# Sheet2.net
KiCad netlist of a schematic drawn in Altium Designer
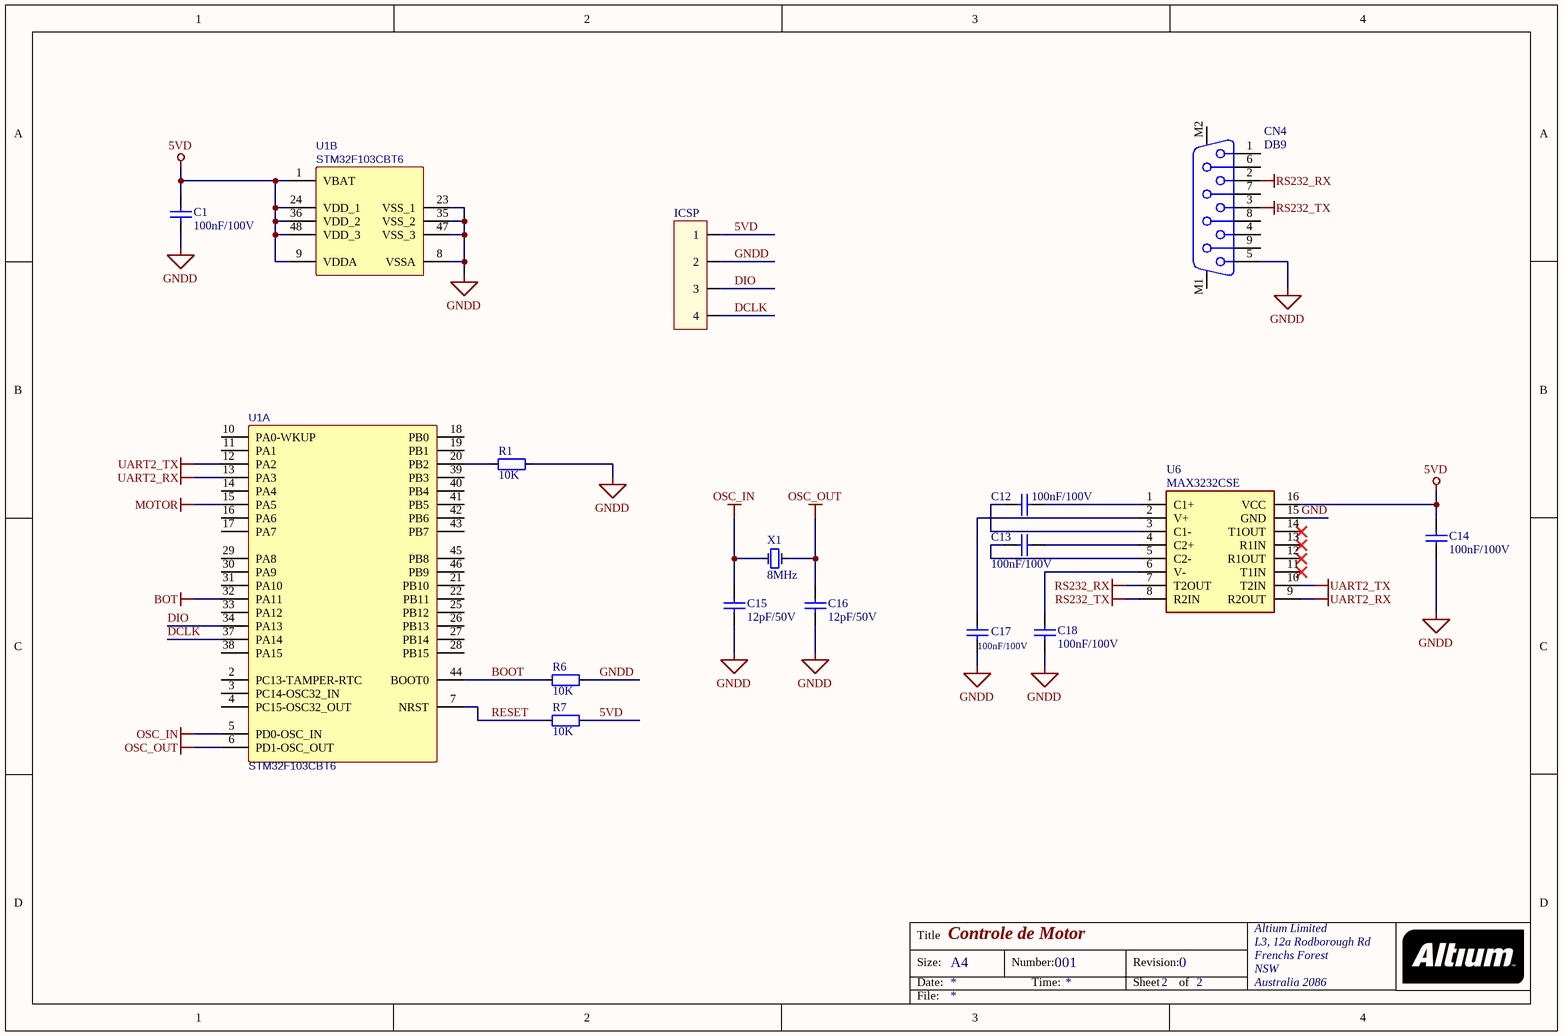
[diagram p0: Sheet2.SchDoc]

(export (version "E")
  (design (tool "Eeschema 10.0.6"))
  (components
    (comp (ref "C1")
      (value "100nF/100V")
      (footprint "0603C-GENERIC")
      (description "Capacitor Cerâmico SMD")
      (libsource (lib "Schlib") (part "Cap Ceramico SMD"))
    )
    (comp (ref "C12")
      (value "100nF/100V")
      (footprint "0603C-GENERIC")
      (description "Capacitor Cerâmico SMD")
      (libsource (lib "Schlib") (part "Cap Ceramico SMD"))
    )
    (comp (ref "C13")
      (value "100nF/100V")
      (footprint "0603C-GENERIC")
      (description "Capacitor Cerâmico SMD")
      (libsource (lib "Schlib") (part "Cap Ceramico SMD"))
    )
    (comp (ref "C14")
      (value "100nF/100V")
      (footprint "0603C-GENERIC")
      (description "Capacitor Cerâmico SMD")
      (libsource (lib "Schlib") (part "Cap Ceramico SMD"))
    )
    (comp (ref "C15")
      (value "12pF/50V")
      (footprint "0603C-GENERIC")
      (description "Capacitor Cerâmico")
      (libsource (lib "Miscellaneous Devices") (part "Cap Ceramico SMD"))
    )
    (comp (ref "C16")
      (value "12pF/50V")
      (footprint "0603C-GENERIC")
      (description "Capacitor Cerâmico")
      (libsource (lib "Miscellaneous Devices") (part "Cap Ceramico SMD"))
    )
    (comp (ref "C17")
      (value "100nF/100V")
      (footprint "0603C-GENERIC")
      (description "Capacitor Cerâmico SMD")
      (libsource (lib "Schlib") (part "Cap Ceramico SMD"))
    )
    (comp (ref "C18")
      (value "100nF/100V")
      (footprint "0603C-GENERIC")
      (description "Capacitor Cerâmico SMD")
      (libsource (lib "Schlib") (part "Cap Ceramico SMD"))
    )
    (comp (ref "CN4")
      (value "DB9")
      (footprint "618009231121")
      (description "Connector DB9")
      (libsource (lib "PUR Conectores") (part "DB9"))
    )
    (comp (ref "ICSP")
      (value "Gravação in circuit")
      (footprint "BP 1x4")
      (description "Barra de Pinos Macho 4p 11,2mm 180º")
      (libsource (lib "Schlib1") (part "BP 1x4 Pinos"))
    )
    (comp (ref "R1")
      (value "10K")
      (footprint "0603R")
      (description "Resistor Metal Filme")
      (libsource (lib "") (part "Res SMD 1206_1"))
    )
    (comp (ref "R6")
      (value "10K")
      (footprint "0603R")
      (description "Resistor Metal Filme")
      (libsource (lib "") (part "Res SMD 1206_1"))
    )
    (comp (ref "R7")
      (value "10K")
      (footprint "0603R")
      (description "Resistor Metal Filme")
      (libsource (lib "Database_PUR") (part "Res SMD 1206"))
    )
    (comp (ref "U1")
      (value "STM32F103CBT6")
      (footprint "LQFP-48")
      (fields (field (name "PART NUMBER") "E2UMIC0000012"))
      (libsource (lib "Schlib1") (part "STM32F103C8T6TR"))
    )
    (comp (ref "U6")
      (value "MAX3232CSE")
      (footprint "PcbLib:SOIC127P600X175-16N")
      (description "Integrated Circuit")
      (libsource (lib "Schlib") (part "MAX232CSE"))
    )
    (comp (ref "X1")
      (value "8MHz")
      (footprint "Cristal HC49S")
      (description "Cristal")
      (libsource (lib "Schlib1") (part "Cristal_CM200C"))
    )
  )
  (nets
    (net (code "2") (name "/BOOT") (class "Default")
      (node (ref "R6") (pin "1") (pinfunction "1_1") (pintype "passive"))
      (node (ref "U1") (pin "44") (pinfunction "BOOT0_44") (pintype "passive"))
    )
    (net (code "3") (name "/DCLK") (class "Default")
      (node (ref "ICSP") (pin "4") (pinfunction "4_4") (pintype "passive"))
      (node (ref "U1") (pin "37") (pinfunction "PA14_37") (pintype "passive"))
    )
    (net (code "4") (name "/DIO") (class "Default")
      (node (ref "ICSP") (pin "3") (pinfunction "3_3") (pintype "passive"))
      (node (ref "U1") (pin "34") (pinfunction "PA13_34") (pintype "passive"))
    )
    (net (code "5") (name "/GND") (class "Default")
      (node (ref "U6") (pin "15") (pinfunction "GND_15") (pintype "passive"))
    )
    (net (code "6") (name "/RESET") (class "Default")
      (node (ref "R7") (pin "2") (pinfunction "2_2") (pintype "passive"))
      (node (ref "U1") (pin "7") (pinfunction "NRST_7") (pintype "passive"))
    )
    (net (code "7") (name "5VD") (class "Default")
      (node (ref "C1") (pin "2") (pinfunction "2_2") (pintype "passive"))
      (node (ref "C14") (pin "1") (pinfunction "1_1") (pintype "passive"))
      (node (ref "ICSP") (pin "1") (pinfunction "1_1") (pintype "passive"))
      (node (ref "R7") (pin "1") (pinfunction "1_1") (pintype "passive"))
      (node (ref "U1") (pin "1") (pinfunction "VBAT_1") (pintype "passive"))
      (node (ref "U1") (pin "24") (pinfunction "VDD_1_24") (pintype "passive"))
      (node (ref "U1") (pin "36") (pinfunction "VDD_2_36") (pintype "passive"))
      (node (ref "U1") (pin "48") (pinfunction "VDD_3_48") (pintype "passive"))
      (node (ref "U1") (pin "9") (pinfunction "VDDA_9") (pintype "passive"))
      (node (ref "U6") (pin "16") (pinfunction "VCC_16") (pintype "passive"))
    )
    (net (code "8") (name "BOT") (class "Default")
      (node (ref "U1") (pin "32") (pinfunction "PA11_32") (pintype "passive"))
    )
    (net (code "9") (name "GNDD") (class "Default")
      (node (ref "C1") (pin "1") (pinfunction "1_1") (pintype "passive"))
      (node (ref "C14") (pin "2") (pinfunction "2_2") (pintype "passive"))
      (node (ref "C15") (pin "1") (pinfunction "1_1") (pintype "passive"))
      (node (ref "C16") (pin "1") (pinfunction "1_1") (pintype "passive"))
      (node (ref "C17") (pin "2") (pinfunction "2_2") (pintype "passive"))
      (node (ref "C18") (pin "2") (pinfunction "2_2") (pintype "passive"))
      (node (ref "CN4") (pin "5") (pinfunction "5_5") (pintype "passive"))
      (node (ref "ICSP") (pin "2") (pinfunction "2_2") (pintype "passive"))
      (node (ref "R1") (pin "2") (pinfunction "2_2") (pintype "passive"))
      (node (ref "R6") (pin "2") (pinfunction "2_2") (pintype "passive"))
      (node (ref "U1") (pin "23") (pinfunction "VSS_1_23") (pintype "passive"))
      (node (ref "U1") (pin "35") (pinfunction "VSS_2_35") (pintype "passive"))
      (node (ref "U1") (pin "47") (pinfunction "VSS_3_47") (pintype "passive"))
      (node (ref "U1") (pin "8") (pinfunction "VSSA_8") (pintype "passive"))
    )
    (net (code "10") (name "MOTOR") (class "Default")
      (node (ref "U1") (pin "15") (pinfunction "PA5_15") (pintype "passive"))
    )
    (net (code "11") (name "Net-(U1A-PB2)") (class "Default")
      (node (ref "R1") (pin "1") (pinfunction "1_1") (pintype "passive"))
      (node (ref "U1") (pin "20") (pinfunction "PB2_20") (pintype "passive"))
    )
    (net (code "12") (name "Net-(U6-C1+)") (class "Default")
      (node (ref "C12") (pin "1") (pinfunction "1_1") (pintype "passive"))
      (node (ref "U6") (pin "1") (pinfunction "C1+_1") (pintype "passive"))
    )
    (net (code "13") (name "Net-(U6-C1-)") (class "Default")
      (node (ref "C12") (pin "2") (pinfunction "2_2") (pintype "passive"))
      (node (ref "U6") (pin "3") (pinfunction "C1-_3") (pintype "passive"))
    )
    (net (code "14") (name "Net-(U6-C2+)") (class "Default")
      (node (ref "C13") (pin "1") (pinfunction "1_1") (pintype "passive"))
      (node (ref "U6") (pin "4") (pinfunction "C2+_4") (pintype "passive"))
    )
    (net (code "15") (name "Net-(U6-C2-)") (class "Default")
      (node (ref "C13") (pin "2") (pinfunction "2_2") (pintype "passive"))
      (node (ref "U6") (pin "5") (pinfunction "C2-_5") (pintype "passive"))
    )
    (net (code "16") (name "Net-(U6-V+)") (class "Default")
      (node (ref "C17") (pin "1") (pinfunction "1_1") (pintype "passive"))
      (node (ref "U6") (pin "2") (pinfunction "V+_2") (pintype "passive"))
    )
    (net (code "17") (name "Net-(U6-V-)") (class "Default")
      (node (ref "C18") (pin "1") (pinfunction "1_1") (pintype "passive"))
      (node (ref "U6") (pin "6") (pinfunction "V-_6") (pintype "passive"))
    )
    (net (code "18") (name "OSC_IN") (class "Default")
      (node (ref "C15") (pin "2") (pinfunction "2_2") (pintype "passive"))
      (node (ref "U1") (pin "5") (pinfunction "PD0-OSC_IN_5") (pintype "passive"))
      (node (ref "X1") (pin "2") (pinfunction "OSC2_2") (pintype "passive"))
    )
    (net (code "19") (name "OSC_OUT") (class "Default")
      (node (ref "C16") (pin "2") (pinfunction "2_2") (pintype "passive"))
      (node (ref "U1") (pin "6") (pinfunction "PD1-OSC_OUT_6") (pintype "passive"))
      (node (ref "X1") (pin "1") (pinfunction "OSC1_1") (pintype "passive"))
    )
    (net (code "20") (name "RS232_RX") (class "Default")
      (node (ref "CN4") (pin "2") (pinfunction "2_2") (pintype "passive"))
      (node (ref "U6") (pin "7") (pinfunction "T2OUT_7") (pintype "passive"))
    )
    (net (code "21") (name "RS232_TX") (class "Default")
      (node (ref "CN4") (pin "3") (pinfunction "3_3") (pintype "passive"))
      (node (ref "U6") (pin "8") (pinfunction "R2IN_8") (pintype "passive"))
    )
    (net (code "22") (name "UART2_RX") (class "Default")
      (node (ref "U1") (pin "13") (pinfunction "PA3_13") (pintype "passive"))
      (node (ref "U6") (pin "9") (pinfunction "R2OUT_9") (pintype "passive"))
    )
    (net (code "23") (name "UART2_TX") (class "Default")
      (node (ref "U1") (pin "12") (pinfunction "PA2_12") (pintype "passive"))
      (node (ref "U6") (pin "10") (pinfunction "T2IN_10") (pintype "passive"))
    )
    (net (code "24") (name "unconnected-(CN4-Pad1)") (class "Default")
      (node (ref "CN4") (pin "1") (pinfunction "1_1") (pintype "passive"))
    )
    (net (code "25") (name "unconnected-(CN4-Pad4)") (class "Default")
      (node (ref "CN4") (pin "4") (pinfunction "4_4") (pintype "passive"))
    )
    (net (code "26") (name "unconnected-(CN4-Pad6)") (class "Default")
      (node (ref "CN4") (pin "6") (pinfunction "6_6") (pintype "passive"))
    )
    (net (code "27") (name "unconnected-(CN4-Pad7)") (class "Default")
      (node (ref "CN4") (pin "7") (pinfunction "7_7") (pintype "passive"))
    )
    (net (code "28") (name "unconnected-(CN4-Pad8)") (class "Default")
      (node (ref "CN4") (pin "8") (pinfunction "8_8") (pintype "passive"))
    )
    (net (code "29") (name "unconnected-(CN4-Pad9)") (class "Default")
      (node (ref "CN4") (pin "9") (pinfunction "9_9") (pintype "passive"))
    )
    (net (code "30") (name "unconnected-(CN4-PadM1)") (class "Default")
      (node (ref "CN4") (pin "M1") (pinfunction "M1_M1") (pintype "passive"))
    )
    (net (code "31") (name "unconnected-(CN4-PadM2)") (class "Default")
      (node (ref "CN4") (pin "M2") (pinfunction "M2_M2") (pintype "passive"))
    )
    (net (code "32") (name "unconnected-(U1A-PA0-WKUP-Pad10)") (class "Default")
      (node (ref "U1") (pin "10") (pinfunction "PA0-WKUP_10") (pintype "passive"))
    )
    (net (code "33") (name "unconnected-(U1A-PA1-Pad11)") (class "Default")
      (node (ref "U1") (pin "11") (pinfunction "PA1_11") (pintype "passive"))
    )
    (net (code "34") (name "unconnected-(U1A-PA4-Pad14)") (class "Default")
      (node (ref "U1") (pin "14") (pinfunction "PA4_14") (pintype "passive"))
    )
    (net (code "35") (name "unconnected-(U1A-PA6-Pad16)") (class "Default")
      (node (ref "U1") (pin "16") (pinfunction "PA6_16") (pintype "passive"))
    )
    (net (code "36") (name "unconnected-(U1A-PA7-Pad17)") (class "Default")
      (node (ref "U1") (pin "17") (pinfunction "PA7_17") (pintype "passive"))
    )
    (net (code "37") (name "unconnected-(U1A-PA8-Pad29)") (class "Default")
      (node (ref "U1") (pin "29") (pinfunction "PA8_29") (pintype "passive"))
    )
    (net (code "38") (name "unconnected-(U1A-PA9-Pad30)") (class "Default")
      (node (ref "U1") (pin "30") (pinfunction "PA9_30") (pintype "passive"))
    )
    (net (code "39") (name "unconnected-(U1A-PA10-Pad31)") (class "Default")
      (node (ref "U1") (pin "31") (pinfunction "PA10_31") (pintype "passive"))
    )
    (net (code "40") (name "unconnected-(U1A-PA12-Pad33)") (class "Default")
      (node (ref "U1") (pin "33") (pinfunction "PA12_33") (pintype "passive"))
    )
    (net (code "41") (name "unconnected-(U1A-PA15-Pad38)") (class "Default")
      (node (ref "U1") (pin "38") (pinfunction "PA15_38") (pintype "passive"))
    )
    (net (code "42") (name "unconnected-(U1A-PB0-Pad18)") (class "Default")
      (node (ref "U1") (pin "18") (pinfunction "PB0_18") (pintype "passive"))
    )
    (net (code "43") (name "unconnected-(U1A-PB1-Pad19)") (class "Default")
      (node (ref "U1") (pin "19") (pinfunction "PB1_19") (pintype "passive"))
    )
    (net (code "44") (name "unconnected-(U1A-PB3-Pad39)") (class "Default")
      (node (ref "U1") (pin "39") (pinfunction "PB3_39") (pintype "passive"))
    )
    (net (code "45") (name "unconnected-(U1A-PB4-Pad40)") (class "Default")
      (node (ref "U1") (pin "40") (pinfunction "PB4_40") (pintype "passive"))
    )
    (net (code "46") (name "unconnected-(U1A-PB5-Pad41)") (class "Default")
      (node (ref "U1") (pin "41") (pinfunction "PB5_41") (pintype "passive"))
    )
    (net (code "47") (name "unconnected-(U1A-PB6-Pad42)") (class "Default")
      (node (ref "U1") (pin "42") (pinfunction "PB6_42") (pintype "passive"))
    )
    (net (code "48") (name "unconnected-(U1A-PB7-Pad43)") (class "Default")
      (node (ref "U1") (pin "43") (pinfunction "PB7_43") (pintype "passive"))
    )
    (net (code "49") (name "unconnected-(U1A-PB8-Pad45)") (class "Default")
      (node (ref "U1") (pin "45") (pinfunction "PB8_45") (pintype "passive"))
    )
    (net (code "50") (name "unconnected-(U1A-PB9-Pad46)") (class "Default")
      (node (ref "U1") (pin "46") (pinfunction "PB9_46") (pintype "passive"))
    )
    (net (code "51") (name "unconnected-(U1A-PB10-Pad21)") (class "Default")
      (node (ref "U1") (pin "21") (pinfunction "PB10_21") (pintype "passive"))
    )
    (net (code "52") (name "unconnected-(U1A-PB11-Pad22)") (class "Default")
      (node (ref "U1") (pin "22") (pinfunction "PB11_22") (pintype "passive"))
    )
    (net (code "53") (name "unconnected-(U1A-PB12-Pad25)") (class "Default")
      (node (ref "U1") (pin "25") (pinfunction "PB12_25") (pintype "passive"))
    )
    (net (code "54") (name "unconnected-(U1A-PB13-Pad26)") (class "Default")
      (node (ref "U1") (pin "26") (pinfunction "PB13_26") (pintype "passive"))
    )
    (net (code "55") (name "unconnected-(U1A-PB14-Pad27)") (class "Default")
      (node (ref "U1") (pin "27") (pinfunction "PB14_27") (pintype "passive"))
    )
    (net (code "56") (name "unconnected-(U1A-PB15-Pad28)") (class "Default")
      (node (ref "U1") (pin "28") (pinfunction "PB15_28") (pintype "passive"))
    )
    (net (code "57") (name "unconnected-(U1A-PC13-TAMPER-RTC-Pad2)") (class "Default")
      (node (ref "U1") (pin "2") (pinfunction "PC13-TAMPER-RTC_2") (pintype "passive"))
    )
    (net (code "58") (name "unconnected-(U1A-PC14-OSC32_IN-Pad3)") (class "Default")
      (node (ref "U1") (pin "3") (pinfunction "PC14-OSC32_IN_3") (pintype "passive"))
    )
    (net (code "59") (name "unconnected-(U1A-PC15-OSC32_OUT-Pad4)") (class "Default")
      (node (ref "U1") (pin "4") (pinfunction "PC15-OSC32_OUT_4") (pintype "passive"))
    )
    (net (code "60") (name "unconnected-(U6-R1IN-Pad13)") (class "Default")
      (node (ref "U6") (pin "13") (pinfunction "R1IN_13") (pintype "passive+no_connect"))
    )
    (net (code "61") (name "unconnected-(U6-R1OUT-Pad12)") (class "Default")
      (node (ref "U6") (pin "12") (pinfunction "R1OUT_12") (pintype "passive+no_connect"))
    )
    (net (code "62") (name "unconnected-(U6-T1IN-Pad11)") (class "Default")
      (node (ref "U6") (pin "11") (pinfunction "T1IN_11") (pintype "passive+no_connect"))
    )
    (net (code "63") (name "unconnected-(U6-T1OUT-Pad14)") (class "Default")
      (node (ref "U6") (pin "14") (pinfunction "T1OUT_14") (pintype "passive+no_connect"))
    )
  )
)
